# 06_SAMA7G54-PIO.net
KiCad netlist of a schematic drawn in Altium Designer
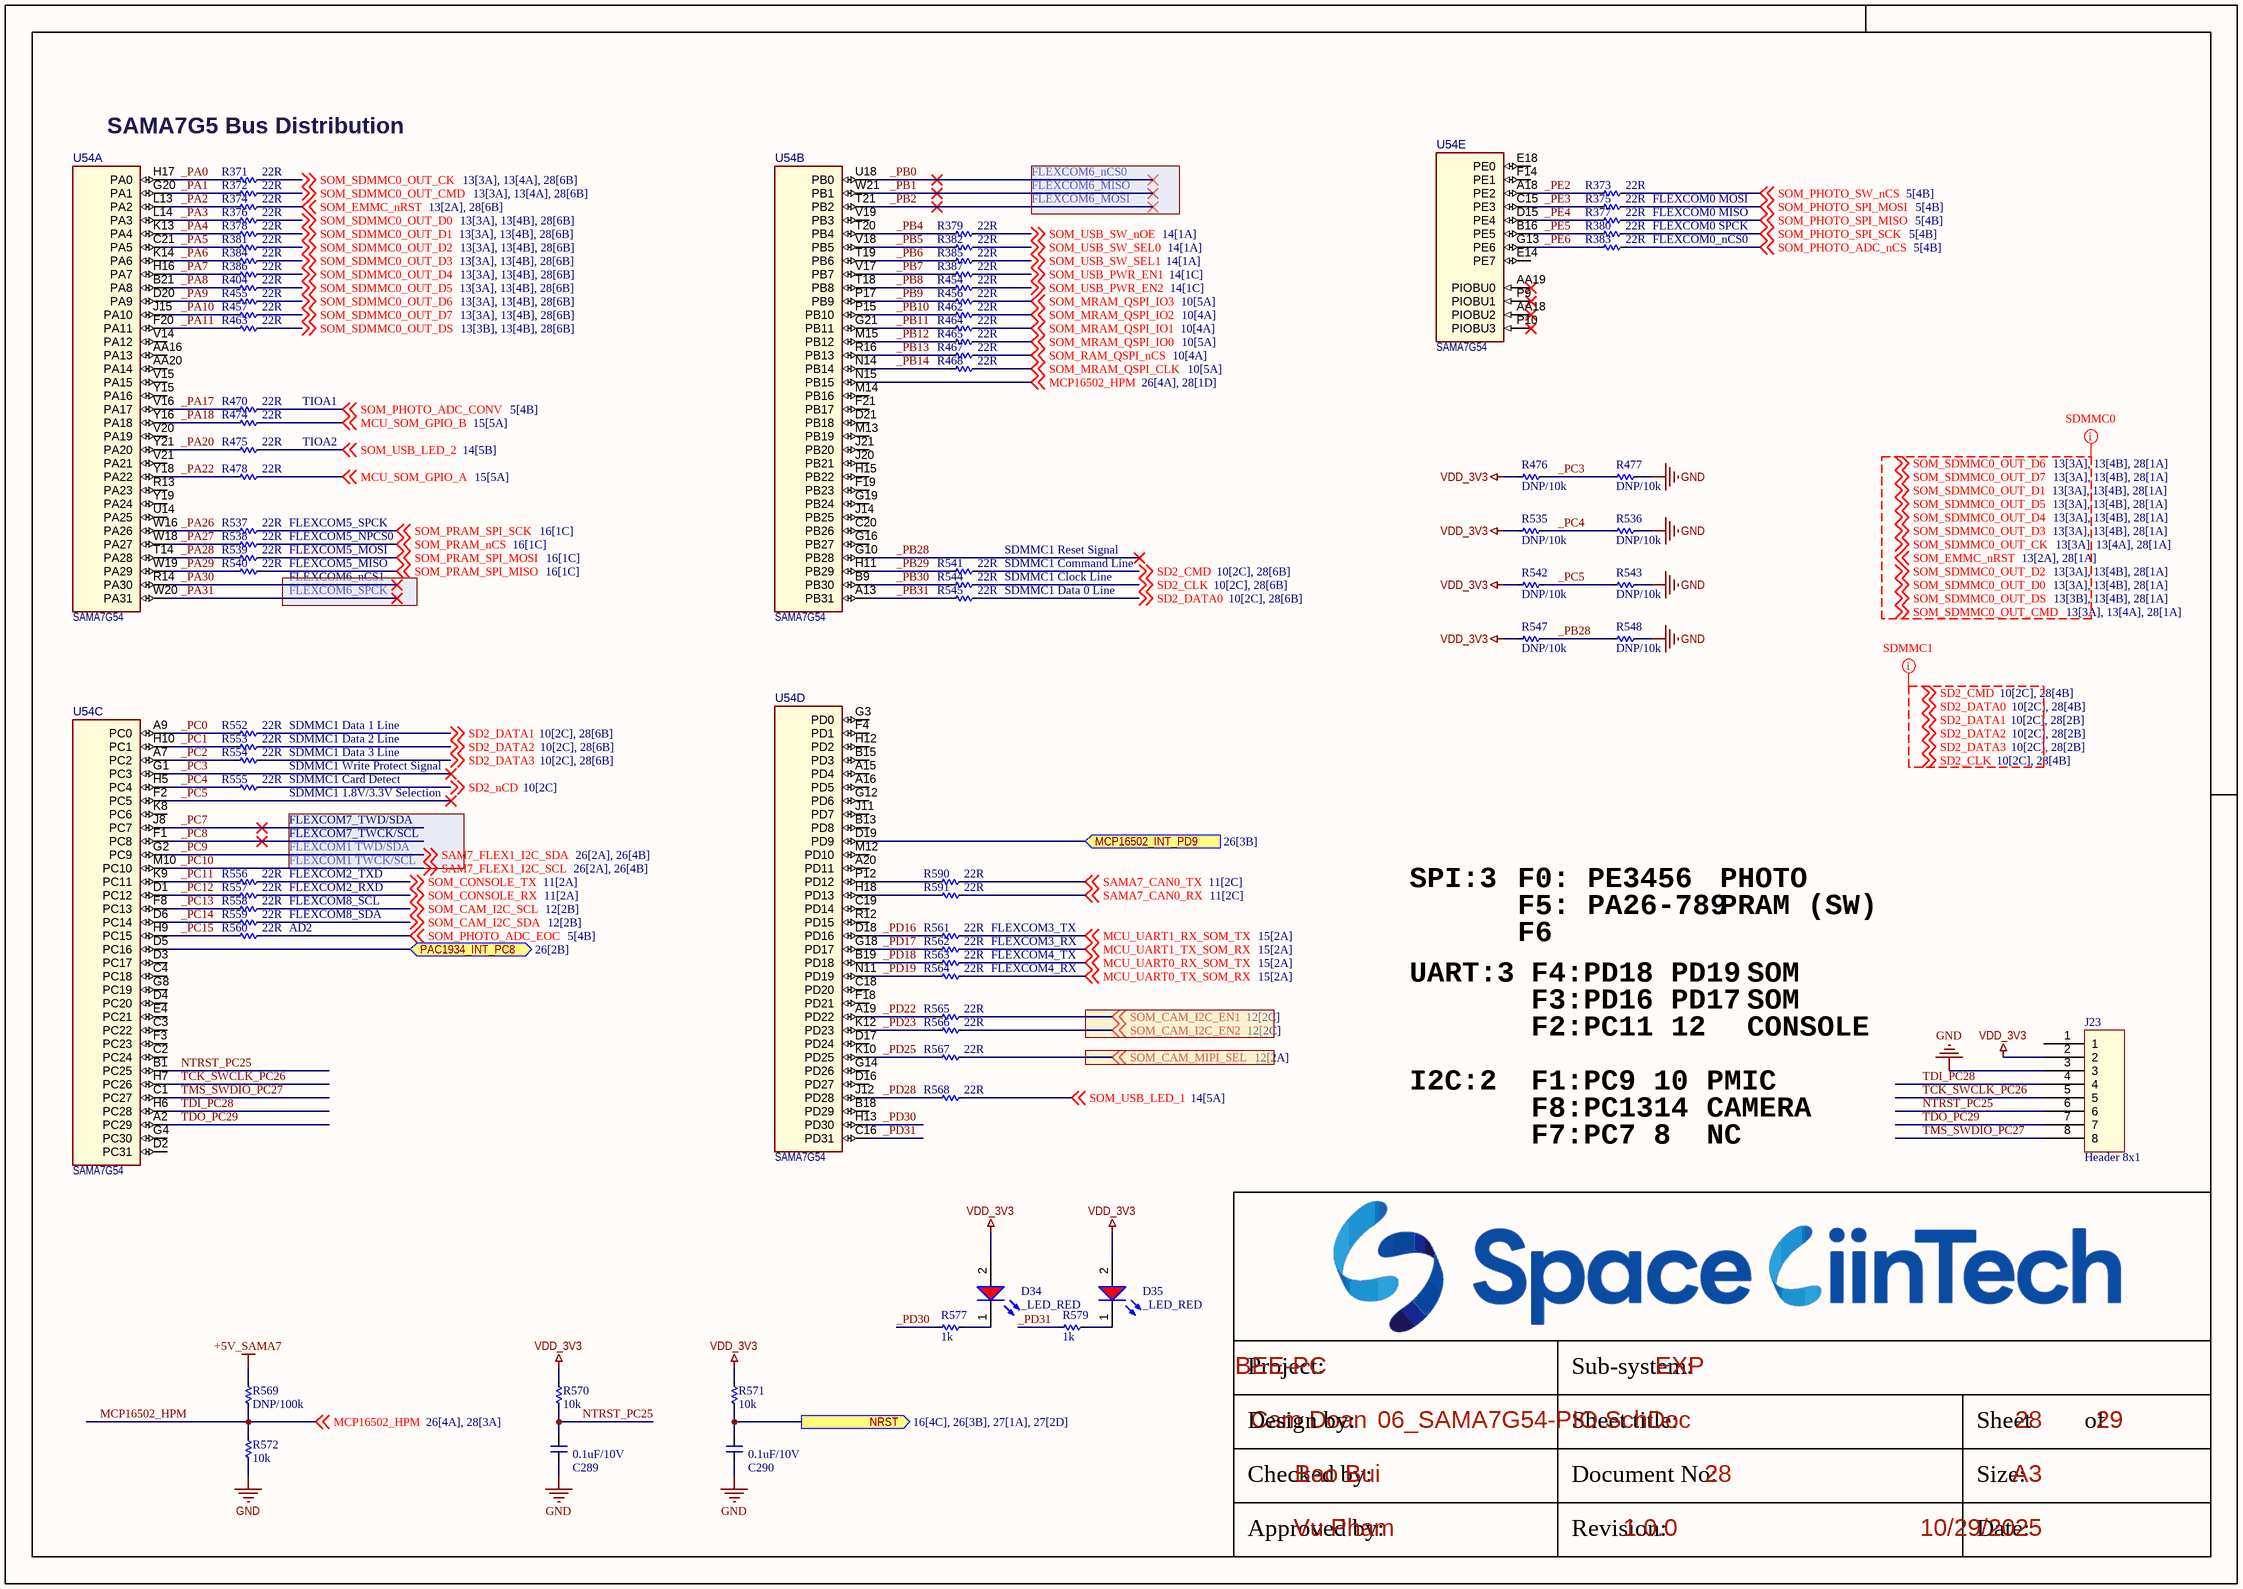
[diagram p0: 06_SAMA7G54-PIO.SchDoc]

(export (version "E")
  (design (tool "Eeschema 10.0.6"))
  (components
    (comp (ref "C289")
      (value "0.1uF/10V")
      (footprint "CAP_C_1005X60")
      (description "CAP CHIP")
      (libsource (lib "LABLIB") (part "_CAP_C_2"))
    )
    (comp (ref "C290")
      (value "0.1uF/10V")
      (footprint "CAP_C_1005X60")
      (description "CAP CHIP")
      (libsource (lib "LABLIB") (part "_CAP_C_2"))
    )
    (comp (ref "D34") (value "_LED_RED") (footprint "LED_0603") (libsource (lib "LABLIB") (part "_LED_RED")))
    (comp (ref "D35") (value "_LED_RED") (footprint "LED_0603") (libsource (lib "LABLIB") (part "_LED_RED")))
    (comp (ref "J23")
      (value "Header 8x1")
      (footprint "Header_254P_8x1")
      (libsource (lib "LABLIB") (part "Header 8x1"))
    )
    (comp (ref "R371")
      (value "22R")
      (footprint "RES_C_0603X30")
      (description "RES")
      (libsource (lib "LABLIB") (part "_RES_B_2"))
    )
    (comp (ref "R372")
      (value "22R")
      (footprint "RES_C_0603X30")
      (description "RES")
      (libsource (lib "LABLIB") (part "_RES_B_2"))
    )
    (comp (ref "R373")
      (value "22R")
      (footprint "RES_C_0603X30")
      (description "RES")
      (libsource (lib "LABLIB") (part "_RES_B_2"))
    )
    (comp (ref "R374")
      (value "22R")
      (footprint "RES_C_0603X30")
      (description "RES")
      (libsource (lib "LABLIB") (part "_RES_B_2"))
    )
    (comp (ref "R375")
      (value "22R")
      (footprint "RES_C_0603X30")
      (description "RES")
      (libsource (lib "LABLIB") (part "_RES_B_2"))
    )
    (comp (ref "R376")
      (value "22R")
      (footprint "RES_C_0603X30")
      (description "RES")
      (libsource (lib "LABLIB") (part "_RES_B_2"))
    )
    (comp (ref "R377")
      (value "22R")
      (footprint "RES_C_0603X30")
      (description "RES")
      (libsource (lib "LABLIB") (part "_RES_B_2"))
    )
    (comp (ref "R378")
      (value "22R")
      (footprint "RES_C_0603X30")
      (description "RES")
      (libsource (lib "LABLIB") (part "_RES_B_2"))
    )
    (comp (ref "R379")
      (value "22R")
      (footprint "RES_C_0603X30")
      (description "RES")
      (libsource (lib "LABLIB") (part "_RES_B_2"))
    )
    (comp (ref "R380")
      (value "22R")
      (footprint "RES_C_0603X30")
      (description "RES")
      (libsource (lib "LABLIB") (part "_RES_B_2"))
    )
    (comp (ref "R381")
      (value "22R")
      (footprint "RES_C_0603X30")
      (description "RES")
      (libsource (lib "LABLIB") (part "_RES_B_2"))
    )
    (comp (ref "R382")
      (value "22R")
      (footprint "RES_C_0603X30")
      (description "RES")
      (libsource (lib "LABLIB") (part "_RES_B_2"))
    )
    (comp (ref "R383")
      (value "22R")
      (footprint "RES_C_0603X30")
      (description "RES")
      (libsource (lib "LABLIB") (part "_RES_B_2"))
    )
    (comp (ref "R384")
      (value "22R")
      (footprint "RES_C_0603X30")
      (description "RES")
      (libsource (lib "LABLIB") (part "_RES_B_2"))
    )
    (comp (ref "R385")
      (value "22R")
      (footprint "RES_C_0603X30")
      (description "RES")
      (libsource (lib "LABLIB") (part "_RES_B_2"))
    )
    (comp (ref "R386")
      (value "22R")
      (footprint "RES_C_0603X30")
      (description "RES")
      (libsource (lib "LABLIB") (part "_RES_B_2"))
    )
    (comp (ref "R387")
      (value "22R")
      (footprint "RES_C_0603X30")
      (description "RES")
      (libsource (lib "LABLIB") (part "_RES_B_2"))
    )
    (comp (ref "R404")
      (value "22R")
      (footprint "RES_C_0603X30")
      (description "RES")
      (libsource (lib "LABLIB") (part "_RES_B_2"))
    )
    (comp (ref "R454")
      (value "22R")
      (footprint "RES_C_0603X30")
      (description "RES")
      (libsource (lib "LABLIB") (part "_RES_B_2"))
    )
    (comp (ref "R455")
      (value "22R")
      (footprint "RES_C_0603X30")
      (description "RES")
      (libsource (lib "LABLIB") (part "_RES_B_2"))
    )
    (comp (ref "R456")
      (value "22R")
      (footprint "RES_C_0603X30")
      (description "RES")
      (libsource (lib "LABLIB") (part "_RES_B_2"))
    )
    (comp (ref "R457")
      (value "22R")
      (footprint "RES_C_0603X30")
      (description "RES")
      (libsource (lib "LABLIB") (part "_RES_B_2"))
    )
    (comp (ref "R462")
      (value "22R")
      (footprint "RES_C_0603X30")
      (description "RES")
      (libsource (lib "LABLIB") (part "_RES_B_2"))
    )
    (comp (ref "R463")
      (value "22R")
      (footprint "RES_C_0603X30")
      (description "RES")
      (libsource (lib "LABLIB") (part "_RES_B_2"))
    )
    (comp (ref "R464")
      (value "22R")
      (footprint "RES_C_0603X30")
      (description "RES")
      (libsource (lib "LABLIB") (part "_RES_B_2"))
    )
    (comp (ref "R465")
      (value "22R")
      (footprint "RES_C_0603X30")
      (description "RES")
      (libsource (lib "LABLIB") (part "_RES_B_2"))
    )
    (comp (ref "R467")
      (value "22R")
      (footprint "RES_C_0603X30")
      (description "RES")
      (libsource (lib "LABLIB") (part "_RES_B_2"))
    )
    (comp (ref "R468")
      (value "22R")
      (footprint "RES_C_0603X30")
      (description "RES")
      (libsource (lib "LABLIB") (part "_RES_B_2"))
    )
    (comp (ref "R470")
      (value "22R")
      (footprint "RES_C_0603X30")
      (description "RES")
      (libsource (lib "LABLIB") (part "_RES_B_2"))
    )
    (comp (ref "R474")
      (value "22R")
      (footprint "RES_C_0603X30")
      (description "RES")
      (libsource (lib "LABLIB") (part "_RES_B_2"))
    )
    (comp (ref "R475")
      (value "22R")
      (footprint "RES_C_0603X30")
      (description "RES")
      (libsource (lib "LABLIB") (part "_RES_B_2"))
    )
    (comp (ref "R476")
      (value "DNP/10k")
      (footprint "RES_C_1005X40")
      (description "RES")
      (libsource (lib "LABLIB") (part "_RES_B_2"))
    )
    (comp (ref "R477")
      (value "DNP/10k")
      (footprint "RES_C_1005X40")
      (description "RES")
      (libsource (lib "LABLIB") (part "_RES_B_2"))
    )
    (comp (ref "R478")
      (value "22R")
      (footprint "RES_C_0603X30")
      (description "RES")
      (libsource (lib "LABLIB") (part "_RES_B_2"))
    )
    (comp (ref "R535")
      (value "DNP/10k")
      (footprint "RES_C_1005X40")
      (description "RES")
      (libsource (lib "LABLIB") (part "_RES_B_2"))
    )
    (comp (ref "R536")
      (value "DNP/10k")
      (footprint "RES_C_1005X40")
      (description "RES")
      (libsource (lib "LABLIB") (part "_RES_B_2"))
    )
    (comp (ref "R537")
      (value "22R")
      (footprint "RES_C_0603X30")
      (description "RES")
      (libsource (lib "LABLIB") (part "_RES_B_2"))
    )
    (comp (ref "R538")
      (value "22R")
      (footprint "RES_C_0603X30")
      (description "RES")
      (libsource (lib "LABLIB") (part "_RES_B_2"))
    )
    (comp (ref "R539")
      (value "22R")
      (footprint "RES_C_0603X30")
      (description "RES")
      (libsource (lib "LABLIB") (part "_RES_B_2"))
    )
    (comp (ref "R540")
      (value "22R")
      (footprint "RES_C_0603X30")
      (description "RES")
      (libsource (lib "LABLIB") (part "_RES_B_2"))
    )
    (comp (ref "R541")
      (value "22R")
      (footprint "RES_C_0603X30")
      (description "RES")
      (libsource (lib "LABLIB") (part "_RES_B_2"))
    )
    (comp (ref "R542")
      (value "DNP/10k")
      (footprint "RES_C_1005X40")
      (description "RES")
      (libsource (lib "LABLIB") (part "_RES_B_2"))
    )
    (comp (ref "R543")
      (value "DNP/10k")
      (footprint "RES_C_1005X40")
      (description "RES")
      (libsource (lib "LABLIB") (part "_RES_B_2"))
    )
    (comp (ref "R544")
      (value "22R")
      (footprint "RES_C_0603X30")
      (description "RES")
      (libsource (lib "LABLIB") (part "_RES_B_2"))
    )
    (comp (ref "R545")
      (value "22R")
      (footprint "RES_C_0603X30")
      (description "RES")
      (libsource (lib "LABLIB") (part "_RES_B_2"))
    )
    (comp (ref "R547")
      (value "DNP/10k")
      (footprint "RES_C_1005X40")
      (description "RES")
      (libsource (lib "LABLIB") (part "_RES_B_2"))
    )
    (comp (ref "R548")
      (value "DNP/10k")
      (footprint "RES_C_1005X40")
      (description "RES")
      (libsource (lib "LABLIB") (part "_RES_B_2"))
    )
    (comp (ref "R552")
      (value "22R")
      (footprint "RES_C_0603X30")
      (description "RES")
      (libsource (lib "LABLIB") (part "_RES_B_2"))
    )
    (comp (ref "R553")
      (value "22R")
      (footprint "RES_C_0603X30")
      (description "RES")
      (libsource (lib "LABLIB") (part "_RES_B_2"))
    )
    (comp (ref "R554")
      (value "22R")
      (footprint "RES_C_0603X30")
      (description "RES")
      (libsource (lib "LABLIB") (part "_RES_B_2"))
    )
    (comp (ref "R555")
      (value "22R")
      (footprint "RES_C_0603X30")
      (description "RES")
      (libsource (lib "LABLIB") (part "_RES_B_2"))
    )
    (comp (ref "R556")
      (value "22R")
      (footprint "RES_C_0603X30")
      (description "RES")
      (libsource (lib "LABLIB") (part "_RES_B_2"))
    )
    (comp (ref "R557")
      (value "22R")
      (footprint "RES_C_0603X30")
      (description "RES")
      (libsource (lib "LABLIB") (part "_RES_B_2"))
    )
    (comp (ref "R558")
      (value "22R")
      (footprint "RES_C_0603X30")
      (description "RES")
      (libsource (lib "LABLIB") (part "_RES_B_2"))
    )
    (comp (ref "R559")
      (value "22R")
      (footprint "RES_C_0603X30")
      (description "RES")
      (libsource (lib "LABLIB") (part "_RES_B_2"))
    )
    (comp (ref "R560")
      (value "22R")
      (footprint "RES_C_0603X30")
      (description "RES")
      (libsource (lib "LABLIB") (part "_RES_B_2"))
    )
    (comp (ref "R561")
      (value "22R")
      (footprint "RES_C_0603X30")
      (description "RES")
      (libsource (lib "LABLIB") (part "_RES_B_2"))
    )
    (comp (ref "R562")
      (value "22R")
      (footprint "RES_C_0603X30")
      (description "RES")
      (libsource (lib "LABLIB") (part "_RES_B_2"))
    )
    (comp (ref "R563")
      (value "22R")
      (footprint "RES_C_0603X30")
      (description "RES")
      (libsource (lib "LABLIB") (part "_RES_B_2"))
    )
    (comp (ref "R564")
      (value "22R")
      (footprint "RES_C_0603X30")
      (description "RES")
      (libsource (lib "LABLIB") (part "_RES_B_2"))
    )
    (comp (ref "R565")
      (value "22R")
      (footprint "RES_C_0603X30")
      (description "RES")
      (libsource (lib "LABLIB") (part "_RES_B_2"))
    )
    (comp (ref "R566")
      (value "22R")
      (footprint "RES_C_0603X30")
      (description "RES")
      (libsource (lib "LABLIB") (part "_RES_B_2"))
    )
    (comp (ref "R567")
      (value "22R")
      (footprint "RES_C_0603X30")
      (description "RES")
      (libsource (lib "LABLIB") (part "_RES_B_2"))
    )
    (comp (ref "R568")
      (value "22R")
      (footprint "RES_C_0603X30")
      (description "RES")
      (libsource (lib "LABLIB") (part "_RES_B_2"))
    )
    (comp (ref "R569")
      (value "DNP/100k")
      (footprint "RES_C_1005X40")
      (description "RES")
      (libsource (lib "LABLIB") (part "_RES_B_2"))
    )
    (comp (ref "R570")
      (value "10k")
      (footprint "RES_C_1005X40")
      (description "RES")
      (libsource (lib "LABLIB") (part "_RES_B_2"))
    )
    (comp (ref "R571")
      (value "10k")
      (footprint "RES_C_1005X40")
      (description "RES")
      (libsource (lib "LABLIB") (part "_RES_B_2"))
    )
    (comp (ref "R572")
      (value "10k")
      (footprint "RES_C_1005X40")
      (description "RES")
      (libsource (lib "LABLIB") (part "_RES_B_2"))
    )
    (comp (ref "R577")
      (value "1k")
      (footprint "RES_C_1005X40")
      (description "RES")
      (libsource (lib "LABLIB") (part "_RES_B_2"))
    )
    (comp (ref "R579")
      (value "1k")
      (footprint "RES_C_1005X40")
      (description "RES")
      (libsource (lib "LABLIB") (part "_RES_B_2"))
    )
    (comp (ref "R590")
      (value "22R")
      (footprint "RES_C_0603X30")
      (description "RES")
      (libsource (lib "LABLIB") (part "_RES_B_2"))
    )
    (comp (ref "R591")
      (value "22R")
      (footprint "RES_C_0603X30")
      (description "RES")
      (libsource (lib "LABLIB") (part "_RES_B_2"))
    )
    (comp (ref "U54")
      (value "SAMA7G54")
      (footprint "TFBGA-343_14x14")
      (description "SAMA7G54 MPU 1000MHz Cortex-A7 TFBGA-343")
      (fields (field (name "OWNER") "Ciprian Abramov"))
      (libsource (lib "MCHP-CDB") (part "SAMA7G54 TFBGA-343"))
    )
  )
  (nets
    (net (code "1") (name "+5V_SAMA7") (class "Default")
      (node (ref "R569") (pin "1") (pinfunction "1_1") (pintype "passive"))
    )
    (net (code "2") (name "/MCP16502_INT_PD9") (class "Default")
      (node (ref "U54") (pin "D19") (pinfunction "PD9_D19") (pintype "bidirectional"))
    )
    (net (code "3") (name "/NRST") (class "Default")
      (node (ref "C290") (pin "2") (pinfunction "2_2") (pintype "passive"))
      (node (ref "R571") (pin "1") (pinfunction "1_1") (pintype "passive"))
    )
    (net (code "4") (name "/NTRST_PC25") (class "Default")
      (node (ref "C289") (pin "2") (pinfunction "2_2") (pintype "passive"))
      (node (ref "J23") (pin "6") (pinfunction "6_6") (pintype "passive"))
      (node (ref "R570") (pin "1") (pinfunction "1_1") (pintype "passive"))
      (node (ref "U54") (pin "B1") (pinfunction "PC25_B1") (pintype "bidirectional"))
    )
    (net (code "5") (name "/PAC1934_INT_PC8") (class "Default")
      (node (ref "U54") (pin "D5") (pinfunction "PC16_D5") (pintype "bidirectional"))
    )
    (net (code "6") (name "/TCK_SWCLK_PC26") (class "Default")
      (node (ref "J23") (pin "5") (pinfunction "5_5") (pintype "passive"))
      (node (ref "U54") (pin "H7") (pinfunction "PC26_H7") (pintype "bidirectional"))
    )
    (net (code "7") (name "/TDI_PC28") (class "Default")
      (node (ref "J23") (pin "4") (pinfunction "4_4") (pintype "passive"))
      (node (ref "U54") (pin "H6") (pinfunction "PC28_H6") (pintype "bidirectional"))
    )
    (net (code "8") (name "/TDO_PC29") (class "Default")
      (node (ref "J23") (pin "7") (pinfunction "7_7") (pintype "passive"))
      (node (ref "U54") (pin "A2") (pinfunction "PC29_A2") (pintype "bidirectional"))
    )
    (net (code "9") (name "/TMS_SWDIO_PC27") (class "Default")
      (node (ref "J23") (pin "8") (pinfunction "8_8") (pintype "passive"))
      (node (ref "U54") (pin "C1") (pinfunction "PC27_C1") (pintype "bidirectional"))
    )
    (net (code "10") (name "/_PA0") (class "Default")
      (node (ref "R371") (pin "2") (pinfunction "2_2") (pintype "passive"))
      (node (ref "U54") (pin "H17") (pinfunction "PA0_H17") (pintype "bidirectional"))
    )
    (net (code "11") (name "/_PA1") (class "Default")
      (node (ref "R372") (pin "2") (pinfunction "2_2") (pintype "passive"))
      (node (ref "U54") (pin "G20") (pinfunction "PA1_G20") (pintype "bidirectional"))
    )
    (net (code "12") (name "/_PA2") (class "Default")
      (node (ref "R374") (pin "2") (pinfunction "2_2") (pintype "passive"))
      (node (ref "U54") (pin "L13") (pinfunction "PA2_L13") (pintype "bidirectional"))
    )
    (net (code "13") (name "/_PA3") (class "Default")
      (node (ref "R376") (pin "2") (pinfunction "2_2") (pintype "passive"))
      (node (ref "U54") (pin "L14") (pinfunction "PA3_L14") (pintype "bidirectional"))
    )
    (net (code "14") (name "/_PA4") (class "Default")
      (node (ref "R378") (pin "2") (pinfunction "2_2") (pintype "passive"))
      (node (ref "U54") (pin "K13") (pinfunction "PA4_K13") (pintype "bidirectional"))
    )
    (net (code "15") (name "/_PA5") (class "Default")
      (node (ref "R381") (pin "2") (pinfunction "2_2") (pintype "passive"))
      (node (ref "U54") (pin "C21") (pinfunction "PA5_C21") (pintype "bidirectional"))
    )
    (net (code "16") (name "/_PA6") (class "Default")
      (node (ref "R384") (pin "2") (pinfunction "2_2") (pintype "passive"))
      (node (ref "U54") (pin "K14") (pinfunction "PA6_K14") (pintype "bidirectional"))
    )
    (net (code "17") (name "/_PA7") (class "Default")
      (node (ref "R386") (pin "2") (pinfunction "2_2") (pintype "passive"))
      (node (ref "U54") (pin "H16") (pinfunction "PA7_H16") (pintype "bidirectional"))
    )
    (net (code "18") (name "/_PA8") (class "Default")
      (node (ref "R404") (pin "2") (pinfunction "2_2") (pintype "passive"))
      (node (ref "U54") (pin "B21") (pinfunction "PA8_B21") (pintype "bidirectional"))
    )
    (net (code "19") (name "/_PA9") (class "Default")
      (node (ref "R455") (pin "2") (pinfunction "2_2") (pintype "passive"))
      (node (ref "U54") (pin "D20") (pinfunction "PA9_D20") (pintype "bidirectional"))
    )
    (net (code "20") (name "/_PA10") (class "Default")
      (node (ref "R457") (pin "2") (pinfunction "2_2") (pintype "passive"))
      (node (ref "U54") (pin "J15") (pinfunction "PA10_J15") (pintype "bidirectional"))
    )
    (net (code "21") (name "/_PA11") (class "Default")
      (node (ref "R463") (pin "2") (pinfunction "2_2") (pintype "passive"))
      (node (ref "U54") (pin "F20") (pinfunction "PA11_F20") (pintype "bidirectional"))
    )
    (net (code "22") (name "/_PA17") (class "Default")
      (node (ref "R470") (pin "2") (pinfunction "2_2") (pintype "passive"))
      (node (ref "U54") (pin "V16") (pinfunction "PA17_V16") (pintype "bidirectional"))
    )
    (net (code "23") (name "/_PA18") (class "Default")
      (node (ref "R474") (pin "2") (pinfunction "2_2") (pintype "passive"))
      (node (ref "U54") (pin "Y16") (pinfunction "PA18_Y16") (pintype "bidirectional"))
    )
    (net (code "24") (name "/_PA20") (class "Default")
      (node (ref "R475") (pin "2") (pinfunction "2_2") (pintype "passive"))
      (node (ref "U54") (pin "Y21") (pinfunction "PA20_Y21") (pintype "bidirectional"))
    )
    (net (code "25") (name "/_PA22") (class "Default")
      (node (ref "R478") (pin "2") (pinfunction "2_2") (pintype "passive"))
      (node (ref "U54") (pin "Y18") (pinfunction "PA22_Y18") (pintype "bidirectional"))
    )
    (net (code "26") (name "/_PA26") (class "Default")
      (node (ref "R537") (pin "2") (pinfunction "2_2") (pintype "passive"))
      (node (ref "U54") (pin "W16") (pinfunction "PA26_W16") (pintype "bidirectional"))
    )
    (net (code "27") (name "/_PA27") (class "Default")
      (node (ref "R538") (pin "2") (pinfunction "2_2") (pintype "passive"))
      (node (ref "U54") (pin "W18") (pinfunction "PA27_W18") (pintype "bidirectional"))
    )
    (net (code "28") (name "/_PA28") (class "Default")
      (node (ref "R539") (pin "2") (pinfunction "2_2") (pintype "passive"))
      (node (ref "U54") (pin "T14") (pinfunction "PA28_T14") (pintype "bidirectional"))
    )
    (net (code "29") (name "/_PA29") (class "Default")
      (node (ref "R540") (pin "2") (pinfunction "2_2") (pintype "passive"))
      (node (ref "U54") (pin "W19") (pinfunction "PA29_W19") (pintype "bidirectional"))
    )
    (net (code "30") (name "/_PA30") (class "Default")
      (node (ref "U54") (pin "R14") (pinfunction "PA30_R14") (pintype "bidirectional+no_connect"))
    )
    (net (code "31") (name "/_PA31") (class "Default")
      (node (ref "U54") (pin "W20") (pinfunction "PA31_W20") (pintype "bidirectional+no_connect"))
    )
    (net (code "32") (name "/_PB0") (class "Default")
      (node (ref "U54") (pin "U18") (pinfunction "PB0_U18") (pintype "bidirectional+no_connect"))
    )
    (net (code "33") (name "/_PB1") (class "Default")
      (node (ref "U54") (pin "W21") (pinfunction "PB1_W21") (pintype "bidirectional+no_connect"))
    )
    (net (code "34") (name "/_PB2") (class "Default")
      (node (ref "U54") (pin "T21") (pinfunction "PB2_T21") (pintype "bidirectional+no_connect"))
    )
    (net (code "35") (name "/_PB4") (class "Default")
      (node (ref "R379") (pin "2") (pinfunction "2_2") (pintype "passive"))
      (node (ref "U54") (pin "T20") (pinfunction "PB4_T20") (pintype "bidirectional"))
    )
    (net (code "36") (name "/_PB5") (class "Default")
      (node (ref "R382") (pin "2") (pinfunction "2_2") (pintype "passive"))
      (node (ref "U54") (pin "V18") (pinfunction "PB5_V18") (pintype "bidirectional"))
    )
    (net (code "37") (name "/_PB6") (class "Default")
      (node (ref "R385") (pin "2") (pinfunction "2_2") (pintype "passive"))
      (node (ref "U54") (pin "T19") (pinfunction "PB6_T19") (pintype "bidirectional"))
    )
    (net (code "38") (name "/_PB7") (class "Default")
      (node (ref "R387") (pin "2") (pinfunction "2_2") (pintype "passive"))
      (node (ref "U54") (pin "V17") (pinfunction "PB7_V17") (pintype "bidirectional"))
    )
    (net (code "39") (name "/_PB8") (class "Default")
      (node (ref "R454") (pin "2") (pinfunction "2_2") (pintype "passive"))
      (node (ref "U54") (pin "T18") (pinfunction "PB8_T18") (pintype "bidirectional"))
    )
    (net (code "40") (name "/_PB9") (class "Default")
      (node (ref "R456") (pin "2") (pinfunction "2_2") (pintype "passive"))
      (node (ref "U54") (pin "P17") (pinfunction "PB9_P17") (pintype "bidirectional"))
    )
    (net (code "41") (name "/_PB10") (class "Default")
      (node (ref "R462") (pin "2") (pinfunction "2_2") (pintype "passive"))
      (node (ref "U54") (pin "P15") (pinfunction "PB10_P15") (pintype "bidirectional"))
    )
    (net (code "42") (name "/_PB11") (class "Default")
      (node (ref "R464") (pin "2") (pinfunction "2_2") (pintype "passive"))
      (node (ref "U54") (pin "G21") (pinfunction "PB11_G21") (pintype "bidirectional"))
    )
    (net (code "43") (name "/_PB12") (class "Default")
      (node (ref "R465") (pin "2") (pinfunction "2_2") (pintype "passive"))
      (node (ref "U54") (pin "M15") (pinfunction "PB12_M15") (pintype "bidirectional"))
    )
    (net (code "44") (name "/_PB13") (class "Default")
      (node (ref "R467") (pin "2") (pinfunction "2_2") (pintype "passive"))
      (node (ref "U54") (pin "R16") (pinfunction "PB13_R16") (pintype "bidirectional"))
    )
    (net (code "45") (name "/_PB14") (class "Default")
      (node (ref "R468") (pin "2") (pinfunction "2_2") (pintype "passive"))
      (node (ref "U54") (pin "N14") (pinfunction "PB14_N14") (pintype "bidirectional"))
    )
    (net (code "46") (name "/_PB28") (class "Default")
      (node (ref "R547") (pin "1") (pinfunction "1_1") (pintype "passive"))
      (node (ref "R548") (pin "2") (pinfunction "2_2") (pintype "passive"))
      (node (ref "U54") (pin "G10") (pinfunction "PB28_G10") (pintype "bidirectional"))
    )
    (net (code "47") (name "/_PB29") (class "Default")
      (node (ref "R541") (pin "2") (pinfunction "2_2") (pintype "passive"))
      (node (ref "U54") (pin "H11") (pinfunction "PB29_H11") (pintype "bidirectional"))
    )
    (net (code "48") (name "/_PB30") (class "Default")
      (node (ref "R544") (pin "2") (pinfunction "2_2") (pintype "passive"))
      (node (ref "U54") (pin "B9") (pinfunction "PB30_B9") (pintype "bidirectional"))
    )
    (net (code "49") (name "/_PB31") (class "Default")
      (node (ref "R545") (pin "2") (pinfunction "2_2") (pintype "passive"))
      (node (ref "U54") (pin "A13") (pinfunction "PB31_A13") (pintype "bidirectional"))
    )
    (net (code "50") (name "/_PC0") (class "Default")
      (node (ref "R552") (pin "2") (pinfunction "2_2") (pintype "passive"))
      (node (ref "U54") (pin "A9") (pinfunction "PC0_A9") (pintype "bidirectional"))
    )
    (net (code "51") (name "/_PC1") (class "Default")
      (node (ref "R553") (pin "2") (pinfunction "2_2") (pintype "passive"))
      (node (ref "U54") (pin "H10") (pinfunction "PC1_H10") (pintype "bidirectional"))
    )
    (net (code "52") (name "/_PC2") (class "Default")
      (node (ref "R554") (pin "2") (pinfunction "2_2") (pintype "passive"))
      (node (ref "U54") (pin "A7") (pinfunction "PC2_A7") (pintype "bidirectional"))
    )
    (net (code "53") (name "/_PC3") (class "Default")
      (node (ref "R476") (pin "1") (pinfunction "1_1") (pintype "passive"))
      (node (ref "R477") (pin "2") (pinfunction "2_2") (pintype "passive"))
      (node (ref "U54") (pin "G1") (pinfunction "PC3_G1") (pintype "bidirectional"))
    )
    (net (code "54") (name "/_PC4") (class "Default")
      (node (ref "R535") (pin "1") (pinfunction "1_1") (pintype "passive"))
      (node (ref "R536") (pin "2") (pinfunction "2_2") (pintype "passive"))
      (node (ref "R555") (pin "2") (pinfunction "2_2") (pintype "passive"))
      (node (ref "U54") (pin "H5") (pinfunction "PC4_H5") (pintype "bidirectional"))
    )
    (net (code "55") (name "/_PC5") (class "Default")
      (node (ref "R542") (pin "1") (pinfunction "1_1") (pintype "passive"))
      (node (ref "R543") (pin "2") (pinfunction "2_2") (pintype "passive"))
      (node (ref "U54") (pin "F2") (pinfunction "PC5_F2") (pintype "bidirectional"))
    )
    (net (code "56") (name "/_PC7") (class "Default")
      (node (ref "U54") (pin "J8") (pinfunction "PC7_J8") (pintype "bidirectional"))
    )
    (net (code "57") (name "/_PC8") (class "Default")
      (node (ref "U54") (pin "F1") (pinfunction "PC8_F1") (pintype "bidirectional"))
    )
    (net (code "58") (name "/_PC11") (class "Default")
      (node (ref "R556") (pin "2") (pinfunction "2_2") (pintype "passive"))
      (node (ref "U54") (pin "K9") (pinfunction "PC11_K9") (pintype "bidirectional"))
    )
    (net (code "59") (name "/_PC12") (class "Default")
      (node (ref "R557") (pin "2") (pinfunction "2_2") (pintype "passive"))
      (node (ref "U54") (pin "D1") (pinfunction "PC12_D1") (pintype "bidirectional"))
    )
    (net (code "60") (name "/_PC13") (class "Default")
      (node (ref "R558") (pin "2") (pinfunction "2_2") (pintype "passive"))
      (node (ref "U54") (pin "F8") (pinfunction "PC13_F8") (pintype "bidirectional"))
    )
    (net (code "61") (name "/_PC14") (class "Default")
      (node (ref "R559") (pin "2") (pinfunction "2_2") (pintype "passive"))
      (node (ref "U54") (pin "D6") (pinfunction "PC14_D6") (pintype "bidirectional"))
    )
    (net (code "62") (name "/_PC15") (class "Default")
      (node (ref "R560") (pin "2") (pinfunction "2_2") (pintype "passive"))
      (node (ref "U54") (pin "H9") (pinfunction "PC15_H9") (pintype "bidirectional"))
    )
    (net (code "63") (name "/_PD16") (class "Default")
      (node (ref "R561") (pin "2") (pinfunction "2_2") (pintype "passive"))
      (node (ref "U54") (pin "D18") (pinfunction "PD16_D18") (pintype "bidirectional"))
    )
    (net (code "64") (name "/_PD17") (class "Default")
      (node (ref "R562") (pin "2") (pinfunction "2_2") (pintype "passive"))
      (node (ref "U54") (pin "G18") (pinfunction "PD17_G18") (pintype "bidirectional"))
    )
    (net (code "65") (name "/_PD18") (class "Default")
      (node (ref "R563") (pin "2") (pinfunction "2_2") (pintype "passive"))
      (node (ref "U54") (pin "B19") (pinfunction "PD18_B19") (pintype "bidirectional"))
    )
    (net (code "66") (name "/_PD19") (class "Default")
      (node (ref "R564") (pin "2") (pinfunction "2_2") (pintype "passive"))
      (node (ref "U54") (pin "N11") (pinfunction "PD19_N11") (pintype "bidirectional"))
    )
    (net (code "67") (name "/_PD22") (class "Default")
      (node (ref "R565") (pin "2") (pinfunction "2_2") (pintype "passive"))
      (node (ref "U54") (pin "A19") (pinfunction "PD22_A19") (pintype "bidirectional"))
    )
    (net (code "68") (name "/_PD23") (class "Default")
      (node (ref "R566") (pin "2") (pinfunction "2_2") (pintype "passive"))
      (node (ref "U54") (pin "K12") (pinfunction "PD23_K12") (pintype "bidirectional"))
    )
    (net (code "69") (name "/_PD25") (class "Default")
      (node (ref "R567") (pin "2") (pinfunction "2_2") (pintype "passive"))
      (node (ref "U54") (pin "K10") (pinfunction "PD25_K10") (pintype "bidirectional"))
    )
    (net (code "70") (name "/_PD28") (class "Default")
      (node (ref "R568") (pin "2") (pinfunction "2_2") (pintype "passive"))
      (node (ref "U54") (pin "J12") (pinfunction "PD28_J12") (pintype "bidirectional"))
    )
    (net (code "71") (name "/_PD30") (class "Default")
      (node (ref "R577") (pin "1") (pinfunction "1_1") (pintype "passive"))
      (node (ref "U54") (pin "H13") (pinfunction "PD30_H13") (pintype "bidirectional"))
    )
    (net (code "72") (name "/_PD31") (class "Default")
      (node (ref "R579") (pin "1") (pinfunction "1_1") (pintype "passive"))
      (node (ref "U54") (pin "C16") (pinfunction "PD31_C16") (pintype "bidirectional"))
    )
    (net (code "73") (name "/_PE2") (class "Default")
      (node (ref "R373") (pin "2") (pinfunction "2_2") (pintype "passive"))
      (node (ref "U54") (pin "A18") (pinfunction "PE2_A18") (pintype "bidirectional"))
    )
    (net (code "74") (name "/_PE3") (class "Default")
      (node (ref "R375") (pin "2") (pinfunction "2_2") (pintype "passive"))
      (node (ref "U54") (pin "C15") (pinfunction "PE3_C15") (pintype "bidirectional"))
    )
    (net (code "75") (name "/_PE4") (class "Default")
      (node (ref "R377") (pin "2") (pinfunction "2_2") (pintype "passive"))
      (node (ref "U54") (pin "D15") (pinfunction "PE4_D15") (pintype "bidirectional"))
    )
    (net (code "76") (name "/_PE5") (class "Default")
      (node (ref "R380") (pin "2") (pinfunction "2_2") (pintype "passive"))
      (node (ref "U54") (pin "B16") (pinfunction "PE5_B16") (pintype "bidirectional"))
    )
    (net (code "77") (name "/_PE6") (class "Default")
      (node (ref "R383") (pin "2") (pinfunction "2_2") (pintype "passive"))
      (node (ref "U54") (pin "G13") (pinfunction "PE6_G13") (pintype "bidirectional"))
    )
    (net (code "78") (name "GND") (class "Default")
      (node (ref "C289") (pin "1") (pinfunction "1_1") (pintype "passive"))
      (node (ref "C290") (pin "1") (pinfunction "1_1") (pintype "passive"))
      (node (ref "J23") (pin "3") (pinfunction "3_3") (pintype "passive"))
      (node (ref "R477") (pin "1") (pinfunction "1_1") (pintype "passive"))
      (node (ref "R536") (pin "1") (pinfunction "1_1") (pintype "passive"))
      (node (ref "R543") (pin "1") (pinfunction "1_1") (pintype "passive"))
      (node (ref "R548") (pin "1") (pinfunction "1_1") (pintype "passive"))
      (node (ref "R572") (pin "2") (pinfunction "2_2") (pintype "passive"))
    )
    (net (code "79") (name "MCP16502_HPM") (class "Default")
      (node (ref "R569") (pin "2") (pinfunction "2_2") (pintype "passive"))
      (node (ref "R572") (pin "1") (pinfunction "1_1") (pintype "passive"))
      (node (ref "U54") (pin "N15") (pinfunction "PB15_N15") (pintype "bidirectional"))
    )
    (net (code "80") (name "MCU_SOM_GPIO_A") (class "Default")
      (node (ref "R478") (pin "1") (pinfunction "1_1") (pintype "passive"))
    )
    (net (code "81") (name "MCU_SOM_GPIO_B") (class "Default")
      (node (ref "R474") (pin "1") (pinfunction "1_1") (pintype "passive"))
    )
    (net (code "82") (name "MCU_UART0_RX_SOM_TX") (class "Default")
      (node (ref "R563") (pin "1") (pinfunction "1_1") (pintype "passive"))
    )
    (net (code "83") (name "MCU_UART0_TX_SOM_RX") (class "Default")
      (node (ref "R564") (pin "1") (pinfunction "1_1") (pintype "passive"))
    )
    (net (code "84") (name "MCU_UART1_RX_SOM_TX") (class "Default")
      (node (ref "R561") (pin "1") (pinfunction "1_1") (pintype "passive"))
    )
    (net (code "85") (name "MCU_UART1_TX_SOM_RX") (class "Default")
      (node (ref "R562") (pin "1") (pinfunction "1_1") (pintype "passive"))
    )
    (net (code "86") (name "Net-(D34-K)") (class "Default")
      (node (ref "D34") (pin "1") (pinfunction "K_1") (pintype "passive"))
      (node (ref "R577") (pin "2") (pinfunction "2_2") (pintype "passive"))
    )
    (net (code "87") (name "Net-(D35-K)") (class "Default")
      (node (ref "D35") (pin "1") (pinfunction "K_1") (pintype "passive"))
      (node (ref "R579") (pin "2") (pinfunction "2_2") (pintype "passive"))
    )
    (net (code "88") (name "Net-(U54D-PD12)") (class "Default")
      (node (ref "R590") (pin "2") (pinfunction "2_2") (pintype "passive"))
      (node (ref "U54") (pin "P12") (pinfunction "PD12_P12") (pintype "bidirectional"))
    )
    (net (code "89") (name "Net-(U54D-PD13)") (class "Default")
      (node (ref "R591") (pin "2") (pinfunction "2_2") (pintype "passive"))
      (node (ref "U54") (pin "H18") (pinfunction "PD13_H18") (pintype "bidirectional"))
    )
    (net (code "90") (name "SAM7_FLEX1_I2C_SCL") (class "Default")
      (node (ref "U54") (pin "M10") (pinfunction "PC10_M10") (pintype "bidirectional"))
    )
    (net (code "91") (name "SAM7_FLEX1_I2C_SDA") (class "Default")
      (node (ref "U54") (pin "G2") (pinfunction "PC9_G2") (pintype "bidirectional"))
    )
    (net (code "92") (name "SAMA7_CAN0_RX") (class "Default")
      (node (ref "R591") (pin "1") (pinfunction "1_1") (pintype "passive"))
    )
    (net (code "93") (name "SAMA7_CAN0_TX") (class "Default")
      (node (ref "R590") (pin "1") (pinfunction "1_1") (pintype "passive"))
    )
    (net (code "94") (name "SD2_CLK") (class "Default")
      (node (ref "R544") (pin "1") (pinfunction "1_1") (pintype "passive"))
    )
    (net (code "95") (name "SD2_CMD") (class "Default")
      (node (ref "R541") (pin "1") (pinfunction "1_1") (pintype "passive"))
    )
    (net (code "96") (name "SD2_DATA0") (class "Default")
      (node (ref "R545") (pin "1") (pinfunction "1_1") (pintype "passive"))
    )
    (net (code "97") (name "SD2_DATA1") (class "Default")
      (node (ref "R552") (pin "1") (pinfunction "1_1") (pintype "passive"))
    )
    (net (code "98") (name "SD2_DATA2") (class "Default")
      (node (ref "R553") (pin "1") (pinfunction "1_1") (pintype "passive"))
    )
    (net (code "99") (name "SD2_DATA3") (class "Default")
      (node (ref "R554") (pin "1") (pinfunction "1_1") (pintype "passive"))
    )
    (net (code "100") (name "SD2_nCD") (class "Default")
      (node (ref "R555") (pin "1") (pinfunction "1_1") (pintype "passive"))
    )
    (net (code "101") (name "SOM_CAM_I2C_EN1") (class "Default")
      (node (ref "R565") (pin "1") (pinfunction "1_1") (pintype "passive"))
    )
    (net (code "102") (name "SOM_CAM_I2C_EN2") (class "Default")
      (node (ref "R566") (pin "1") (pinfunction "1_1") (pintype "passive"))
    )
    (net (code "103") (name "SOM_CAM_I2C_SCL") (class "Default")
      (node (ref "R558") (pin "1") (pinfunction "1_1") (pintype "passive"))
    )
    (net (code "104") (name "SOM_CAM_I2C_SDA") (class "Default")
      (node (ref "R559") (pin "1") (pinfunction "1_1") (pintype "passive"))
    )
    (net (code "105") (name "SOM_CAM_MIPI_SEL") (class "Default")
      (node (ref "R567") (pin "1") (pinfunction "1_1") (pintype "passive"))
    )
    (net (code "106") (name "SOM_CONSOLE_RX") (class "Default")
      (node (ref "R557") (pin "1") (pinfunction "1_1") (pintype "passive"))
    )
    (net (code "107") (name "SOM_CONSOLE_TX") (class "Default")
      (node (ref "R556") (pin "1") (pinfunction "1_1") (pintype "passive"))
    )
    (net (code "108") (name "SOM_EMMC_nRST") (class "Default")
      (node (ref "R374") (pin "1") (pinfunction "1_1") (pintype "passive"))
    )
    (net (code "109") (name "SOM_MRAM_QSPI_CLK") (class "Default")
      (node (ref "R468") (pin "1") (pinfunction "1_1") (pintype "passive"))
    )
    (net (code "110") (name "SOM_MRAM_QSPI_IO0") (class "Default")
      (node (ref "R465") (pin "1") (pinfunction "1_1") (pintype "passive"))
    )
    (net (code "111") (name "SOM_MRAM_QSPI_IO1") (class "Default")
      (node (ref "R464") (pin "1") (pinfunction "1_1") (pintype "passive"))
    )
    (net (code "112") (name "SOM_MRAM_QSPI_IO2") (class "Default")
      (node (ref "R462") (pin "1") (pinfunction "1_1") (pintype "passive"))
    )
    (net (code "113") (name "SOM_MRAM_QSPI_IO3") (class "Default")
      (node (ref "R456") (pin "1") (pinfunction "1_1") (pintype "passive"))
    )
    (net (code "114") (name "SOM_PHOTO_ADC_CONV") (class "Default")
      (node (ref "R470") (pin "1") (pinfunction "1_1") (pintype "passive"))
    )
    (net (code "115") (name "SOM_PHOTO_ADC_EOC") (class "Default")
      (node (ref "R560") (pin "1") (pinfunction "1_1") (pintype "passive"))
    )
    (net (code "116") (name "SOM_PHOTO_ADC_nCS") (class "Default")
      (node (ref "R383") (pin "1") (pinfunction "1_1") (pintype "passive"))
    )
    (net (code "117") (name "SOM_PHOTO_SPI_MISO") (class "Default")
      (node (ref "R377") (pin "1") (pinfunction "1_1") (pintype "passive"))
    )
    (net (code "118") (name "SOM_PHOTO_SPI_MOSI") (class "Default")
      (node (ref "R375") (pin "1") (pinfunction "1_1") (pintype "passive"))
    )
    (net (code "119") (name "SOM_PHOTO_SPI_SCK") (class "Default")
      (node (ref "R380") (pin "1") (pinfunction "1_1") (pintype "passive"))
    )
    (net (code "120") (name "SOM_PHOTO_SW_nCS") (class "Default")
      (node (ref "R373") (pin "1") (pinfunction "1_1") (pintype "passive"))
    )
    (net (code "121") (name "SOM_PRAM_SPI_MISO") (class "Default")
      (node (ref "R540") (pin "1") (pinfunction "1_1") (pintype "passive"))
    )
    (net (code "122") (name "SOM_PRAM_SPI_MOSI") (class "Default")
      (node (ref "R539") (pin "1") (pinfunction "1_1") (pintype "passive"))
    )
    (net (code "123") (name "SOM_PRAM_SPI_SCK") (class "Default")
      (node (ref "R537") (pin "1") (pinfunction "1_1") (pintype "passive"))
    )
    (net (code "124") (name "SOM_PRAM_nCS") (class "Default")
      (node (ref "R538") (pin "1") (pinfunction "1_1") (pintype "passive"))
    )
    (net (code "125") (name "SOM_RAM_QSPI_nCS") (class "Default")
      (node (ref "R467") (pin "1") (pinfunction "1_1") (pintype "passive"))
    )
    (net (code "126") (name "SOM_SDMMC0_OUT_CK") (class "Default")
      (node (ref "R371") (pin "1") (pinfunction "1_1") (pintype "passive"))
    )
    (net (code "127") (name "SOM_SDMMC0_OUT_CMD") (class "Default")
      (node (ref "R372") (pin "1") (pinfunction "1_1") (pintype "passive"))
    )
    (net (code "128") (name "SOM_SDMMC0_OUT_D0") (class "Default")
      (node (ref "R376") (pin "1") (pinfunction "1_1") (pintype "passive"))
    )
    (net (code "129") (name "SOM_SDMMC0_OUT_D1") (class "Default")
      (node (ref "R378") (pin "1") (pinfunction "1_1") (pintype "passive"))
    )
    (net (code "130") (name "SOM_SDMMC0_OUT_D2") (class "Default")
      (node (ref "R381") (pin "1") (pinfunction "1_1") (pintype "passive"))
    )
    (net (code "131") (name "SOM_SDMMC0_OUT_D3") (class "Default")
      (node (ref "R384") (pin "1") (pinfunction "1_1") (pintype "passive"))
    )
    (net (code "132") (name "SOM_SDMMC0_OUT_D4") (class "Default")
      (node (ref "R386") (pin "1") (pinfunction "1_1") (pintype "passive"))
    )
    (net (code "133") (name "SOM_SDMMC0_OUT_D5") (class "Default")
      (node (ref "R404") (pin "1") (pinfunction "1_1") (pintype "passive"))
    )
    (net (code "134") (name "SOM_SDMMC0_OUT_D6") (class "Default")
      (node (ref "R455") (pin "1") (pinfunction "1_1") (pintype "passive"))
    )
    (net (code "135") (name "SOM_SDMMC0_OUT_D7") (class "Default")
      (node (ref "R457") (pin "1") (pinfunction "1_1") (pintype "passive"))
    )
    (net (code "136") (name "SOM_SDMMC0_OUT_DS") (class "Default")
      (node (ref "R463") (pin "1") (pinfunction "1_1") (pintype "passive"))
    )
    (net (code "137") (name "SOM_USB_LED_1") (class "Default")
      (node (ref "R568") (pin "1") (pinfunction "1_1") (pintype "passive"))
    )
    (net (code "138") (name "SOM_USB_LED_2") (class "Default")
      (node (ref "R475") (pin "1") (pinfunction "1_1") (pintype "passive"))
    )
    (net (code "139") (name "SOM_USB_PWR_EN1") (class "Default")
      (node (ref "R387") (pin "1") (pinfunction "1_1") (pintype "passive"))
    )
    (net (code "140") (name "SOM_USB_PWR_EN2") (class "Default")
      (node (ref "R454") (pin "1") (pinfunction "1_1") (pintype "passive"))
    )
    (net (code "141") (name "SOM_USB_SW_SEL0") (class "Default")
      (node (ref "R382") (pin "1") (pinfunction "1_1") (pintype "passive"))
    )
    (net (code "142") (name "SOM_USB_SW_SEL1") (class "Default")
      (node (ref "R385") (pin "1") (pinfunction "1_1") (pintype "passive"))
    )
    (net (code "143") (name "SOM_USB_SW_nOE") (class "Default")
      (node (ref "R379") (pin "1") (pinfunction "1_1") (pintype "passive"))
    )
    (net (code "144") (name "VDD_3V3") (class "Default")
      (node (ref "D34") (pin "2") (pinfunction "A_2") (pintype "passive"))
      (node (ref "D35") (pin "2") (pinfunction "A_2") (pintype "passive"))
      (node (ref "J23") (pin "2") (pinfunction "2_2") (pintype "passive"))
      (node (ref "R476") (pin "2") (pinfunction "2_2") (pintype "passive"))
      (node (ref "R535") (pin "2") (pinfunction "2_2") (pintype "passive"))
      (node (ref "R542") (pin "2") (pinfunction "2_2") (pintype "passive"))
      (node (ref "R547") (pin "2") (pinfunction "2_2") (pintype "passive"))
      (node (ref "R570") (pin "2") (pinfunction "2_2") (pintype "passive"))
      (node (ref "R571") (pin "2") (pinfunction "2_2") (pintype "passive"))
    )
    (net (code "145") (name "unconnected-(J23-Pad1)") (class "Default")
      (node (ref "J23") (pin "1") (pinfunction "1_1") (pintype "passive"))
    )
    (net (code "146") (name "unconnected-(U54A-PA12-PadV14)") (class "Default")
      (node (ref "U54") (pin "V14") (pinfunction "PA12_V14") (pintype "bidirectional"))
    )
    (net (code "147") (name "unconnected-(U54A-PA13-PadAA16)") (class "Default")
      (node (ref "U54") (pin "AA16") (pinfunction "PA13_AA16") (pintype "bidirectional"))
    )
    (net (code "148") (name "unconnected-(U54A-PA14-PadAA20)") (class "Default")
      (node (ref "U54") (pin "AA20") (pinfunction "PA14_AA20") (pintype "bidirectional"))
    )
    (net (code "149") (name "unconnected-(U54A-PA15-PadV15)") (class "Default")
      (node (ref "U54") (pin "V15") (pinfunction "PA15_V15") (pintype "bidirectional"))
    )
    (net (code "150") (name "unconnected-(U54A-PA16-PadY15)") (class "Default")
      (node (ref "U54") (pin "Y15") (pinfunction "PA16_Y15") (pintype "bidirectional"))
    )
    (net (code "151") (name "unconnected-(U54A-PA19-PadV20)") (class "Default")
      (node (ref "U54") (pin "V20") (pinfunction "PA19_V20") (pintype "bidirectional"))
    )
    (net (code "152") (name "unconnected-(U54A-PA21-PadV21)") (class "Default")
      (node (ref "U54") (pin "V21") (pinfunction "PA21_V21") (pintype "bidirectional"))
    )
    (net (code "153") (name "unconnected-(U54A-PA23-PadR13)") (class "Default")
      (node (ref "U54") (pin "R13") (pinfunction "PA23_R13") (pintype "bidirectional"))
    )
    (net (code "154") (name "unconnected-(U54A-PA24-PadY19)") (class "Default")
      (node (ref "U54") (pin "Y19") (pinfunction "PA24_Y19") (pintype "bidirectional"))
    )
    (net (code "155") (name "unconnected-(U54A-PA25-PadU14)") (class "Default")
      (node (ref "U54") (pin "U14") (pinfunction "PA25_U14") (pintype "bidirectional"))
    )
    (net (code "156") (name "unconnected-(U54B-PB3-PadV19)") (class "Default")
      (node (ref "U54") (pin "V19") (pinfunction "PB3_V19") (pintype "bidirectional"))
    )
    (net (code "157") (name "unconnected-(U54B-PB16-PadM14)") (class "Default")
      (node (ref "U54") (pin "M14") (pinfunction "PB16_M14") (pintype "bidirectional"))
    )
    (net (code "158") (name "unconnected-(U54B-PB17-PadF21)") (class "Default")
      (node (ref "U54") (pin "F21") (pinfunction "PB17_F21") (pintype "bidirectional"))
    )
    (net (code "159") (name "unconnected-(U54B-PB18-PadD21)") (class "Default")
      (node (ref "U54") (pin "D21") (pinfunction "PB18_D21") (pintype "bidirectional"))
    )
    (net (code "160") (name "unconnected-(U54B-PB19-PadM13)") (class "Default")
      (node (ref "U54") (pin "M13") (pinfunction "PB19_M13") (pintype "bidirectional"))
    )
    (net (code "161") (name "unconnected-(U54B-PB20-PadJ21)") (class "Default")
      (node (ref "U54") (pin "J21") (pinfunction "PB20_J21") (pintype "bidirectional"))
    )
    (net (code "162") (name "unconnected-(U54B-PB21-PadJ20)") (class "Default")
      (node (ref "U54") (pin "J20") (pinfunction "PB21_J20") (pintype "bidirectional"))
    )
    (net (code "163") (name "unconnected-(U54B-PB22-PadH15)") (class "Default")
      (node (ref "U54") (pin "H15") (pinfunction "PB22_H15") (pintype "bidirectional"))
    )
    (net (code "164") (name "unconnected-(U54B-PB23-PadF19)") (class "Default")
      (node (ref "U54") (pin "F19") (pinfunction "PB23_F19") (pintype "bidirectional"))
    )
    (net (code "165") (name "unconnected-(U54B-PB24-PadG19)") (class "Default")
      (node (ref "U54") (pin "G19") (pinfunction "PB24_G19") (pintype "bidirectional"))
    )
    (net (code "166") (name "unconnected-(U54B-PB25-PadJ14)") (class "Default")
      (node (ref "U54") (pin "J14") (pinfunction "PB25_J14") (pintype "bidirectional"))
    )
    (net (code "167") (name "unconnected-(U54B-PB26-PadC20)") (class "Default")
      (node (ref "U54") (pin "C20") (pinfunction "PB26_C20") (pintype "bidirectional"))
    )
    (net (code "168") (name "unconnected-(U54B-PB27-PadG16)") (class "Default")
      (node (ref "U54") (pin "G16") (pinfunction "PB27_G16") (pintype "bidirectional"))
    )
    (net (code "169") (name "unconnected-(U54C-PC6-PadK8)") (class "Default")
      (node (ref "U54") (pin "K8") (pinfunction "PC6_K8") (pintype "bidirectional"))
    )
    (net (code "170") (name "unconnected-(U54C-PC17-PadD3)") (class "Default")
      (node (ref "U54") (pin "D3") (pinfunction "PC17_D3") (pintype "bidirectional"))
    )
    (net (code "171") (name "unconnected-(U54C-PC18-PadC4)") (class "Default")
      (node (ref "U54") (pin "C4") (pinfunction "PC18_C4") (pintype "bidirectional"))
    )
    (net (code "172") (name "unconnected-(U54C-PC19-PadG8)") (class "Default")
      (node (ref "U54") (pin "G8") (pinfunction "PC19_G8") (pintype "bidirectional"))
    )
    (net (code "173") (name "unconnected-(U54C-PC20-PadD4)") (class "Default")
      (node (ref "U54") (pin "D4") (pinfunction "PC20_D4") (pintype "bidirectional"))
    )
    (net (code "174") (name "unconnected-(U54C-PC21-PadE4)") (class "Default")
      (node (ref "U54") (pin "E4") (pinfunction "PC21_E4") (pintype "bidirectional"))
    )
    (net (code "175") (name "unconnected-(U54C-PC22-PadC3)") (class "Default")
      (node (ref "U54") (pin "C3") (pinfunction "PC22_C3") (pintype "bidirectional"))
    )
    (net (code "176") (name "unconnected-(U54C-PC23-PadF3)") (class "Default")
      (node (ref "U54") (pin "F3") (pinfunction "PC23_F3") (pintype "bidirectional"))
    )
    (net (code "177") (name "unconnected-(U54C-PC24-PadC2)") (class "Default")
      (node (ref "U54") (pin "C2") (pinfunction "PC24_C2") (pintype "bidirectional"))
    )
    (net (code "178") (name "unconnected-(U54C-PC30-PadG4)") (class "Default")
      (node (ref "U54") (pin "G4") (pinfunction "PC30_G4") (pintype "bidirectional"))
    )
    (net (code "179") (name "unconnected-(U54C-PC31-PadD2)") (class "Default")
      (node (ref "U54") (pin "D2") (pinfunction "PC31_D2") (pintype "bidirectional"))
    )
    (net (code "180") (name "unconnected-(U54D-PD0-PadG3)") (class "Default")
      (node (ref "U54") (pin "G3") (pinfunction "PD0_G3") (pintype "bidirectional"))
    )
    (net (code "181") (name "unconnected-(U54D-PD1-PadF4)") (class "Default")
      (node (ref "U54") (pin "F4") (pinfunction "PD1_F4") (pintype "bidirectional"))
    )
    (net (code "182") (name "unconnected-(U54D-PD2-PadH12)") (class "Default")
      (node (ref "U54") (pin "H12") (pinfunction "PD2_H12") (pintype "bidirectional"))
    )
    (net (code "183") (name "unconnected-(U54D-PD3-PadB15)") (class "Default")
      (node (ref "U54") (pin "B15") (pinfunction "PD3_B15") (pintype "bidirectional"))
    )
    (net (code "184") (name "unconnected-(U54D-PD4-PadA15)") (class "Default")
      (node (ref "U54") (pin "A15") (pinfunction "PD4_A15") (pintype "bidirectional"))
    )
    (net (code "185") (name "unconnected-(U54D-PD5-PadA16)") (class "Default")
      (node (ref "U54") (pin "A16") (pinfunction "PD5_A16") (pintype "bidirectional"))
    )
    (net (code "186") (name "unconnected-(U54D-PD6-PadG12)") (class "Default")
      (node (ref "U54") (pin "G12") (pinfunction "PD6_G12") (pintype "bidirectional"))
    )
    (net (code "187") (name "unconnected-(U54D-PD7-PadJ11)") (class "Default")
      (node (ref "U54") (pin "J11") (pinfunction "PD7_J11") (pintype "bidirectional"))
    )
    (net (code "188") (name "unconnected-(U54D-PD8-PadB13)") (class "Default")
      (node (ref "U54") (pin "B13") (pinfunction "PD8_B13") (pintype "bidirectional"))
    )
    (net (code "189") (name "unconnected-(U54D-PD10-PadM12)") (class "Default")
      (node (ref "U54") (pin "M12") (pinfunction "PD10_M12") (pintype "bidirectional"))
    )
    (net (code "190") (name "unconnected-(U54D-PD11-PadA20)") (class "Default")
      (node (ref "U54") (pin "A20") (pinfunction "PD11_A20") (pintype "bidirectional"))
    )
    (net (code "191") (name "unconnected-(U54D-PD14-PadC19)") (class "Default")
      (node (ref "U54") (pin "C19") (pinfunction "PD14_C19") (pintype "bidirectional"))
    )
    (net (code "192") (name "unconnected-(U54D-PD15-PadR12)") (class "Default")
      (node (ref "U54") (pin "R12") (pinfunction "PD15_R12") (pintype "bidirectional"))
    )
    (net (code "193") (name "unconnected-(U54D-PD20-PadC18)") (class "Default")
      (node (ref "U54") (pin "C18") (pinfunction "PD20_C18") (pintype "bidirectional"))
    )
    (net (code "194") (name "unconnected-(U54D-PD21-PadF18)") (class "Default")
      (node (ref "U54") (pin "F18") (pinfunction "PD21_F18") (pintype "bidirectional"))
    )
    (net (code "195") (name "unconnected-(U54D-PD24-PadD17)") (class "Default")
      (node (ref "U54") (pin "D17") (pinfunction "PD24_D17") (pintype "bidirectional"))
    )
    (net (code "196") (name "unconnected-(U54D-PD26-PadG14)") (class "Default")
      (node (ref "U54") (pin "G14") (pinfunction "PD26_G14") (pintype "bidirectional"))
    )
    (net (code "197") (name "unconnected-(U54D-PD27-PadD16)") (class "Default")
      (node (ref "U54") (pin "D16") (pinfunction "PD27_D16") (pintype "bidirectional"))
    )
    (net (code "198") (name "unconnected-(U54D-PD29-PadB18)") (class "Default")
      (node (ref "U54") (pin "B18") (pinfunction "PD29_B18") (pintype "bidirectional"))
    )
    (net (code "199") (name "unconnected-(U54E-PE0-PadE18)") (class "Default")
      (node (ref "U54") (pin "E18") (pinfunction "PE0_E18") (pintype "bidirectional"))
    )
    (net (code "200") (name "unconnected-(U54E-PE1-PadF14)") (class "Default")
      (node (ref "U54") (pin "F14") (pinfunction "PE1_F14") (pintype "bidirectional"))
    )
    (net (code "201") (name "unconnected-(U54E-PE7-PadE14)") (class "Default")
      (node (ref "U54") (pin "E14") (pinfunction "PE7_E14") (pintype "bidirectional"))
    )
    (net (code "202") (name "unconnected-(U54E-PIOBU0-PadAA19)") (class "Default")
      (node (ref "U54") (pin "AA19") (pinfunction "PIOBU0_AA19") (pintype "input+no_connect"))
    )
    (net (code "203") (name "unconnected-(U54E-PIOBU1-PadP9)") (class "Default")
      (node (ref "U54") (pin "P9") (pinfunction "PIOBU1_P9") (pintype "input+no_connect"))
    )
    (net (code "204") (name "unconnected-(U54E-PIOBU2-PadAA18)") (class "Default")
      (node (ref "U54") (pin "AA18") (pinfunction "PIOBU2_AA18") (pintype "input+no_connect"))
    )
    (net (code "205") (name "unconnected-(U54E-PIOBU3-PadP10)") (class "Default")
      (node (ref "U54") (pin "P10") (pinfunction "PIOBU3_P10") (pintype "input+no_connect"))
    )
  )
)
